# miniecu-v1_0c.net
KiCad netlist of a schematic drawn in EAGLE
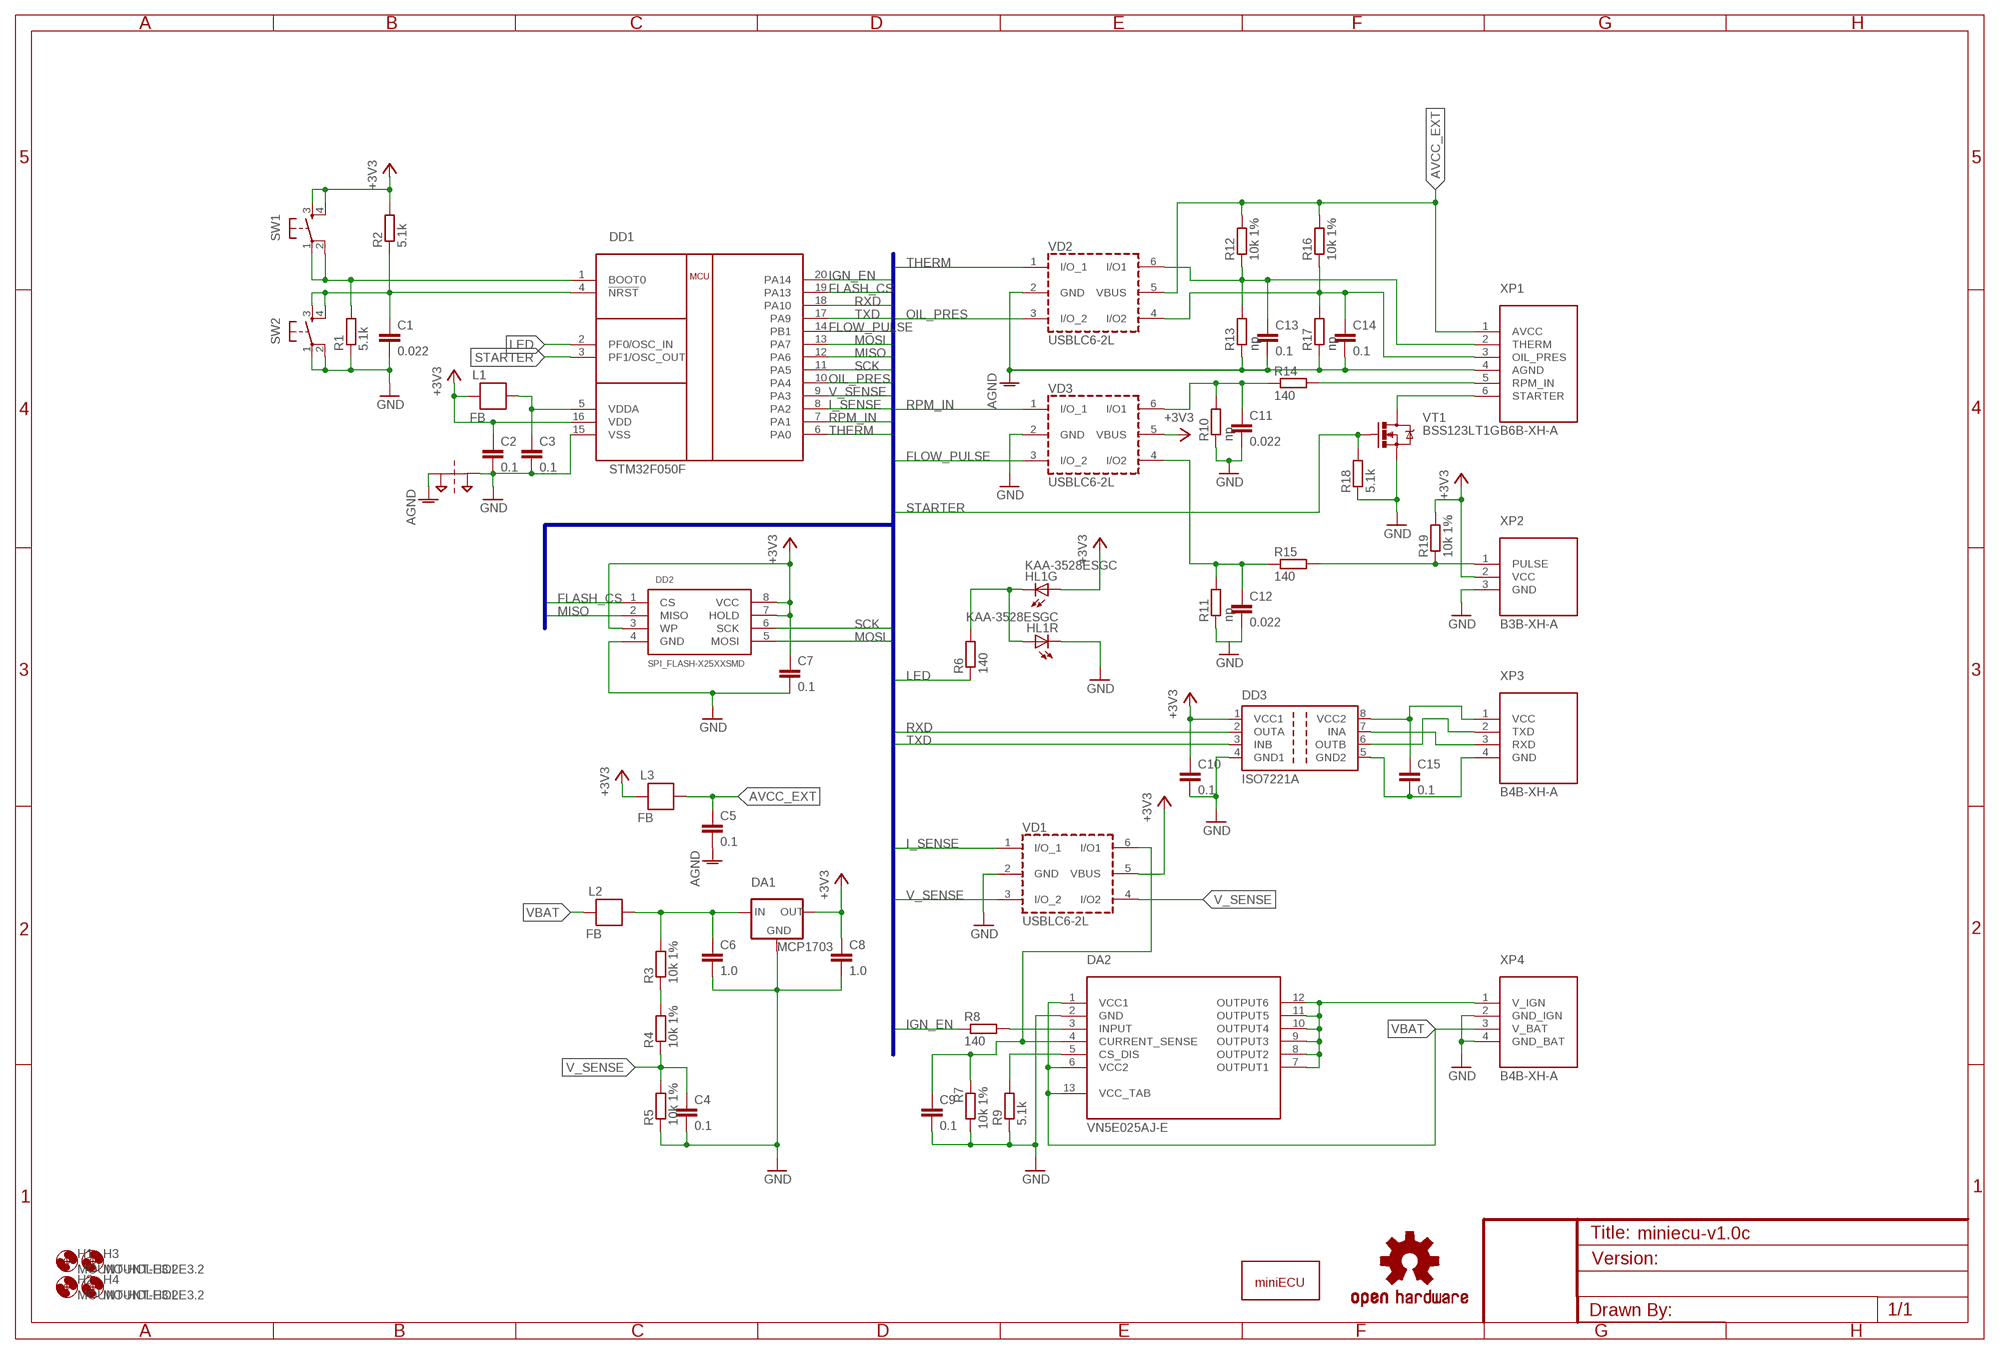
[diagram p0: schematic, sheet 1]

(export (version "E")
  (design (tool "Eeschema 10.0.6"))
  (components
    (comp (ref "C1")
      (value "0.022")
      (footprint "eagle-import:C0603")
      (libsource (lib "eagle-import") (part "C-EUC0603"))
    )
    (comp (ref "C2")
      (value "0.1")
      (footprint "eagle-import:C0603")
      (libsource (lib "eagle-import") (part "C-EUC0603"))
    )
    (comp (ref "C3")
      (value "0.1")
      (footprint "eagle-import:C0603")
      (libsource (lib "eagle-import") (part "C-EUC0603"))
    )
    (comp (ref "C4")
      (value "0.1")
      (footprint "eagle-import:C0603")
      (libsource (lib "eagle-import") (part "C-EUC0603"))
    )
    (comp (ref "C5")
      (value "0.1")
      (footprint "eagle-import:C0603")
      (libsource (lib "eagle-import") (part "C-EUC0603"))
    )
    (comp (ref "C6")
      (value "1.0")
      (footprint "eagle-import:C0805")
      (libsource (lib "eagle-import") (part "C-EUC0805"))
    )
    (comp (ref "C7")
      (value "0.1")
      (footprint "eagle-import:C0603")
      (libsource (lib "eagle-import") (part "C-EUC0603"))
    )
    (comp (ref "C8")
      (value "1.0")
      (footprint "eagle-import:C0805")
      (libsource (lib "eagle-import") (part "C-EUC0805"))
    )
    (comp (ref "C9")
      (value "0.1")
      (footprint "eagle-import:C0603")
      (libsource (lib "eagle-import") (part "C-EUC0603"))
    )
    (comp (ref "C10")
      (value "0.1")
      (footprint "eagle-import:C0603")
      (libsource (lib "eagle-import") (part "C-EUC0603"))
    )
    (comp (ref "C11")
      (value "0.022")
      (footprint "eagle-import:C0603")
      (libsource (lib "eagle-import") (part "C-EUC0603"))
    )
    (comp (ref "C12")
      (value "0.022")
      (footprint "eagle-import:C0603")
      (libsource (lib "eagle-import") (part "C-EUC0603"))
    )
    (comp (ref "C13")
      (value "0.1")
      (footprint "eagle-import:C0603")
      (libsource (lib "eagle-import") (part "C-EUC0603"))
    )
    (comp (ref "C14")
      (value "0.1")
      (footprint "eagle-import:C0603")
      (libsource (lib "eagle-import") (part "C-EUC0603"))
    )
    (comp (ref "C15")
      (value "0.1")
      (footprint "eagle-import:C0603")
      (libsource (lib "eagle-import") (part "C-EUC0603"))
    )
    (comp (ref "DA1")
      (value "MCP1703")
      (footprint "eagle-import:SOT23")
      (libsource (lib "eagle-import") (part "MCP1700SOT-23"))
    )
    (comp (ref "DA2")
      (value "VN5E025AJ-E")
      (footprint "eagle-import:POWERSSO-12")
      (libsource (lib "eagle-import") (part "VN5E025AJ-E"))
    )
    (comp (ref "DD1")
      (value "STM32F050F")
      (footprint "eagle-import:TSSOP20")
      (libsource (lib "eagle-import") (part "STM32F050F"))
    )
    (comp (ref "DD2")
      (value "SPI_FLASH-X25XXSMD")
      (footprint "eagle-import:SO08")
      (libsource (lib "eagle-import") (part "SPI_FLASH-X25XXSMD"))
    )
    (comp (ref "DD3")
      (value "ISO7221A")
      (footprint "eagle-import:SO-08")
      (fields (field (name "MPN") "ISO7221AD"))
      (libsource (lib "eagle-import") (part "ISO7221A"))
    )
    (comp (ref "H1")
      (value "MOUNT-HOLE3.2")
      (footprint "eagle-import:3,2")
      (libsource (lib "eagle-import") (part "MOUNT-HOLE3.2"))
    )
    (comp (ref "H2")
      (value "MOUNT-HOLE3.2")
      (footprint "eagle-import:3,2")
      (libsource (lib "eagle-import") (part "MOUNT-HOLE3.2"))
    )
    (comp (ref "H3")
      (value "MOUNT-HOLE3.2")
      (footprint "eagle-import:3,2")
      (libsource (lib "eagle-import") (part "MOUNT-HOLE3.2"))
    )
    (comp (ref "H4")
      (value "MOUNT-HOLE3.2")
      (footprint "eagle-import:3,2")
      (libsource (lib "eagle-import") (part "MOUNT-HOLE3.2"))
    )
    (comp (ref "HL1")
      (value "KAA-3528ESGC")
      (footprint "eagle-import:KA-3528")
      (libsource (lib "eagle-import") (part "KAA-3528ESGC"))
    )
    (comp (ref "L1")
      (value "FB")
      (footprint "eagle-import:0603")
      (libsource (lib "eagle-import") (part "FB"))
    )
    (comp (ref "L2")
      (value "FB")
      (footprint "eagle-import:0603")
      (libsource (lib "eagle-import") (part "FB"))
    )
    (comp (ref "L3")
      (value "FB")
      (footprint "eagle-import:0603")
      (libsource (lib "eagle-import") (part "FB"))
    )
    (comp (ref "LOGO1")
      (value "OSHW-LOGOL")
      (footprint "eagle-import:OSHW-LOGO-L")
      (libsource (lib "eagle-import") (part "OSHW-LOGOL"))
    )
    (comp (ref "LOGO2")
      (value "MINIECU_LOGO")
      (footprint "eagle-import:MINIECU_LOGO")
      (libsource (lib "eagle-import") (part "MINIECU_LOGO"))
    )
    (comp (ref "PT1")
      (value "2PT_GND_TIE")
      (footprint "eagle-import:2PT_GND_TIE")
      (libsource (lib "eagle-import") (part "2PT_GND_TIE"))
    )
    (comp (ref "R1")
      (value "5.1k")
      (footprint "eagle-import:R0603")
      (libsource (lib "eagle-import") (part "R-EU_R0603"))
    )
    (comp (ref "R2")
      (value "5.1k")
      (footprint "eagle-import:R0603")
      (libsource (lib "eagle-import") (part "R-EU_R0603"))
    )
    (comp (ref "R3")
      (value "10k 1%")
      (footprint "eagle-import:R0805")
      (libsource (lib "eagle-import") (part "R-EU_R0805"))
    )
    (comp (ref "R4")
      (value "10k 1%")
      (footprint "eagle-import:R0805")
      (libsource (lib "eagle-import") (part "R-EU_R0805"))
    )
    (comp (ref "R5")
      (value "10k 1%")
      (footprint "eagle-import:R0805")
      (libsource (lib "eagle-import") (part "R-EU_R0805"))
    )
    (comp (ref "R6")
      (value "140")
      (footprint "eagle-import:R0603")
      (libsource (lib "eagle-import") (part "R-EU_R0603"))
    )
    (comp (ref "R7")
      (value "10k 1%")
      (footprint "eagle-import:R0805")
      (libsource (lib "eagle-import") (part "R-EU_R0805"))
    )
    (comp (ref "R8")
      (value "140")
      (footprint "eagle-import:R0603")
      (libsource (lib "eagle-import") (part "R-EU_R0603"))
    )
    (comp (ref "R9")
      (value "5.1k")
      (footprint "eagle-import:R0603")
      (libsource (lib "eagle-import") (part "R-EU_R0603"))
    )
    (comp (ref "R10")
      (value "np")
      (footprint "eagle-import:R0603")
      (libsource (lib "eagle-import") (part "R-EU_R0603"))
    )
    (comp (ref "R11")
      (value "np")
      (footprint "eagle-import:R0603")
      (libsource (lib "eagle-import") (part "R-EU_R0603"))
    )
    (comp (ref "R12")
      (value "10k 1%")
      (footprint "eagle-import:R0805")
      (libsource (lib "eagle-import") (part "R-EU_R0805"))
    )
    (comp (ref "R13")
      (value "np")
      (footprint "eagle-import:R0805")
      (libsource (lib "eagle-import") (part "R-EU_R0805"))
    )
    (comp (ref "R14")
      (value "140")
      (footprint "eagle-import:R0603")
      (libsource (lib "eagle-import") (part "R-EU_R0603"))
    )
    (comp (ref "R15")
      (value "140")
      (footprint "eagle-import:R0603")
      (libsource (lib "eagle-import") (part "R-EU_R0603"))
    )
    (comp (ref "R16")
      (value "10k 1%")
      (footprint "eagle-import:R0805")
      (libsource (lib "eagle-import") (part "R-EU_R0805"))
    )
    (comp (ref "R17")
      (value "np")
      (footprint "eagle-import:R0805")
      (libsource (lib "eagle-import") (part "R-EU_R0805"))
    )
    (comp (ref "R18")
      (value "5.1k")
      (footprint "eagle-import:R0603")
      (libsource (lib "eagle-import") (part "R-EU_R0603"))
    )
    (comp (ref "R19")
      (value "10k 1%")
      (footprint "eagle-import:R0805")
      (libsource (lib "eagle-import") (part "R-EU_R0805"))
    )
    (comp (ref "SW1")
      (value "TAC_SWITCHSMD")
      (footprint "eagle-import:TACTILE_SWITCH_SMD")
      (libsource (lib "eagle-import") (part "TAC_SWITCHSMD"))
    )
    (comp (ref "SW2")
      (value "TAC_SWITCHSMD")
      (footprint "eagle-import:TACTILE_SWITCH_SMD")
      (libsource (lib "eagle-import") (part "TAC_SWITCHSMD"))
    )
    (comp (ref "VD1")
      (value "USBLC6-2L")
      (footprint "eagle-import:SOT-23-6L")
      (libsource (lib "eagle-import") (part "USBLC6-2SC6"))
    )
    (comp (ref "VD2")
      (value "USBLC6-2L")
      (footprint "eagle-import:SOT-23-6L")
      (libsource (lib "eagle-import") (part "USBLC6-2SC6"))
    )
    (comp (ref "VD3")
      (value "USBLC6-2L")
      (footprint "eagle-import:SOT-23-6L")
      (libsource (lib "eagle-import") (part "USBLC6-2SC6"))
    )
    (comp (ref "VT1")
      (value "BSS123LT1G")
      (footprint "eagle-import:SOT23")
      (libsource (lib "eagle-import") (part "MOSFET-NCHANNELBSS123LT1G"))
    )
    (comp (ref "XP1")
      (value "B6B-XH-A")
      (footprint "eagle-import:B6B-XH")
      (libsource (lib "eagle-import") (part "SENSORS-B6B-XH-A"))
    )
    (comp (ref "XP2")
      (value "B3B-XH-A")
      (footprint "eagle-import:B3B-XH")
      (libsource (lib "eagle-import") (part "FLOW_SENS-B3B-XH-A"))
    )
    (comp (ref "XP3")
      (value "B4B-XH-A")
      (footprint "eagle-import:B4B-XH")
      (libsource (lib "eagle-import") (part "UART-B4B-XH-A"))
    )
    (comp (ref "XP4")
      (value "B4B-XH-A")
      (footprint "eagle-import:B4B-XH")
      (libsource (lib "eagle-import") (part "IGN_POWER-B4B-XH-A"))
    )
  )
  (nets
    (net (code "1") (name "+3V3") (class "Default")
      (node (ref "C10") (pin "1") (pinfunction "1_1") (pintype "passive"))
      (node (ref "C2") (pin "1") (pinfunction "1_1") (pintype "passive"))
      (node (ref "C7") (pin "1") (pinfunction "1_1") (pintype "passive"))
      (node (ref "C8") (pin "1") (pinfunction "1_1") (pintype "passive"))
      (node (ref "DA1") (pin "2") (pinfunction "OUT_2") (pintype "passive"))
      (node (ref "DD1") (pin "16") (pinfunction "VDD_16") (pintype "power_in"))
      (node (ref "DD2") (pin "3") (pinfunction "WP_3") (pintype "bidirectional"))
      (node (ref "DD2") (pin "7") (pinfunction "HOLD_7") (pintype "bidirectional"))
      (node (ref "DD2") (pin "8") (pinfunction "VCC_8") (pintype "bidirectional"))
      (node (ref "DD3") (pin "1") (pinfunction "VCC1_1") (pintype "power_in"))
      (node (ref "HL1") (pin "4") (pinfunction "A_4") (pintype "passive"))
      (node (ref "L1") (pin "2") (pinfunction "P$2_2") (pintype "bidirectional"))
      (node (ref "L3") (pin "2") (pinfunction "P$2_2") (pintype "bidirectional"))
      (node (ref "R19") (pin "2") (pinfunction "2_2") (pintype "passive"))
      (node (ref "R2") (pin "2") (pinfunction "2_2") (pintype "passive"))
      (node (ref "SW1") (pin "3") (pinfunction "3_3") (pintype "passive"))
      (node (ref "SW1") (pin "4") (pinfunction "4_4") (pintype "passive"))
      (node (ref "VD1") (pin "5") (pinfunction "VBUS_5") (pintype "bidirectional"))
      (node (ref "VD3") (pin "5") (pinfunction "VBUS_5") (pintype "bidirectional"))
      (node (ref "XP2") (pin "2") (pinfunction "VCC_2") (pintype "passive"))
    )
    (net (code "2") (name "/FLASH_CS") (class "Default")
      (node (ref "DD1") (pin "19") (pinfunction "PA13_19") (pintype "bidirectional"))
      (node (ref "DD2") (pin "1") (pinfunction "CS_1") (pintype "bidirectional"))
    )
    (net (code "3") (name "/FLOW_PULSE") (class "Default")
      (node (ref "C12") (pin "1") (pinfunction "1_1") (pintype "passive"))
      (node (ref "DD1") (pin "14") (pinfunction "PB1_14") (pintype "bidirectional"))
      (node (ref "R11") (pin "2") (pinfunction "2_2") (pintype "passive"))
      (node (ref "R15") (pin "1") (pinfunction "1_1") (pintype "passive"))
      (node (ref "VD3") (pin "3") (pinfunction "I/O_2_3") (pintype "bidirectional"))
      (node (ref "VD3") (pin "4") (pinfunction "I/O2_4") (pintype "bidirectional"))
    )
    (net (code "4") (name "/IGN_EN") (class "Default")
      (node (ref "DD1") (pin "20") (pinfunction "PA14_20") (pintype "bidirectional"))
      (node (ref "R8") (pin "1") (pinfunction "1_1") (pintype "passive"))
    )
    (net (code "5") (name "/I_SENSE") (class "Default")
      (node (ref "C9") (pin "1") (pinfunction "1_1") (pintype "passive"))
      (node (ref "DA2") (pin "4") (pinfunction "CURRENT_SENSE_4") (pintype "bidirectional"))
      (node (ref "DD1") (pin "8") (pinfunction "PA2_8") (pintype "bidirectional"))
      (node (ref "R7") (pin "1") (pinfunction "1_1") (pintype "passive"))
      (node (ref "VD1") (pin "1") (pinfunction "I/O_1_1") (pintype "bidirectional"))
      (node (ref "VD1") (pin "6") (pinfunction "I/O1_6") (pintype "bidirectional"))
    )
    (net (code "6") (name "/MISO") (class "Default")
      (node (ref "DD1") (pin "12") (pinfunction "PA6_12") (pintype "bidirectional"))
      (node (ref "DD2") (pin "2") (pinfunction "MISO_2") (pintype "bidirectional"))
    )
    (net (code "7") (name "/MOSI") (class "Default")
      (node (ref "DD1") (pin "13") (pinfunction "PA7_13") (pintype "bidirectional"))
      (node (ref "DD2") (pin "5") (pinfunction "MOSI_5") (pintype "bidirectional"))
    )
    (net (code "8") (name "/OIL_PRES") (class "Default")
      (node (ref "C14") (pin "1") (pinfunction "1_1") (pintype "passive"))
      (node (ref "DD1") (pin "10") (pinfunction "PA4_10") (pintype "bidirectional"))
      (node (ref "R16") (pin "1") (pinfunction "1_1") (pintype "passive"))
      (node (ref "R17") (pin "2") (pinfunction "2_2") (pintype "passive"))
      (node (ref "VD2") (pin "3") (pinfunction "I/O_2_3") (pintype "bidirectional"))
      (node (ref "VD2") (pin "4") (pinfunction "I/O2_4") (pintype "bidirectional"))
      (node (ref "XP1") (pin "3") (pinfunction "OIL_PRES_3") (pintype "passive"))
    )
    (net (code "9") (name "/RPM_IN") (class "Default")
      (node (ref "C11") (pin "1") (pinfunction "1_1") (pintype "passive"))
      (node (ref "DD1") (pin "7") (pinfunction "PA1_7") (pintype "bidirectional"))
      (node (ref "R10") (pin "2") (pinfunction "2_2") (pintype "passive"))
      (node (ref "R14") (pin "1") (pinfunction "1_1") (pintype "passive"))
      (node (ref "VD3") (pin "1") (pinfunction "I/O_1_1") (pintype "bidirectional"))
      (node (ref "VD3") (pin "6") (pinfunction "I/O1_6") (pintype "bidirectional"))
    )
    (net (code "10") (name "/RXD") (class "Default")
      (node (ref "DD1") (pin "18") (pinfunction "PA10_18") (pintype "bidirectional"))
      (node (ref "DD3") (pin "2") (pinfunction "OUTA_2") (pintype "output"))
    )
    (net (code "11") (name "/SCK") (class "Default")
      (node (ref "DD1") (pin "11") (pinfunction "PA5_11") (pintype "bidirectional"))
      (node (ref "DD2") (pin "6") (pinfunction "SCK_6") (pintype "bidirectional"))
    )
    (net (code "12") (name "/THERM") (class "Default")
      (node (ref "C13") (pin "1") (pinfunction "1_1") (pintype "passive"))
      (node (ref "DD1") (pin "6") (pinfunction "PA0_6") (pintype "bidirectional"))
      (node (ref "R12") (pin "1") (pinfunction "1_1") (pintype "passive"))
      (node (ref "R13") (pin "2") (pinfunction "2_2") (pintype "passive"))
      (node (ref "VD2") (pin "1") (pinfunction "I/O_1_1") (pintype "bidirectional"))
      (node (ref "VD2") (pin "6") (pinfunction "I/O1_6") (pintype "bidirectional"))
      (node (ref "XP1") (pin "2") (pinfunction "THERM_2") (pintype "passive"))
    )
    (net (code "13") (name "/TXD") (class "Default")
      (node (ref "DD1") (pin "17") (pinfunction "PA9_17") (pintype "bidirectional"))
      (node (ref "DD3") (pin "3") (pinfunction "INB_3") (pintype "input"))
    )
    (net (code "14") (name "AGND") (class "Default")
      (node (ref "C13") (pin "2") (pinfunction "2_2") (pintype "passive"))
      (node (ref "C14") (pin "2") (pinfunction "2_2") (pintype "passive"))
      (node (ref "C5") (pin "2") (pinfunction "2_2") (pintype "passive"))
      (node (ref "PT1") (pin "P$1") (pinfunction "P$1_P$1") (pintype "bidirectional"))
      (node (ref "R13") (pin "1") (pinfunction "1_1") (pintype "passive"))
      (node (ref "R17") (pin "1") (pinfunction "1_1") (pintype "passive"))
      (node (ref "VD2") (pin "2") (pinfunction "GND_2") (pintype "bidirectional"))
      (node (ref "XP1") (pin "4") (pinfunction "AGND_4") (pintype "passive"))
    )
    (net (code "15") (name "AVCC_EXT") (class "Default")
      (node (ref "C5") (pin "1") (pinfunction "1_1") (pintype "passive"))
      (node (ref "L3") (pin "1") (pinfunction "P$1_1") (pintype "bidirectional"))
      (node (ref "R12") (pin "2") (pinfunction "2_2") (pintype "passive"))
      (node (ref "R16") (pin "2") (pinfunction "2_2") (pintype "passive"))
      (node (ref "VD2") (pin "5") (pinfunction "VBUS_5") (pintype "bidirectional"))
      (node (ref "XP1") (pin "1") (pinfunction "AVCC_1") (pintype "passive"))
    )
    (net (code "16") (name "GND") (class "Default")
      (node (ref "C1") (pin "2") (pinfunction "2_2") (pintype "passive"))
      (node (ref "C10") (pin "2") (pinfunction "2_2") (pintype "passive"))
      (node (ref "C11") (pin "2") (pinfunction "2_2") (pintype "passive"))
      (node (ref "C12") (pin "2") (pinfunction "2_2") (pintype "passive"))
      (node (ref "C2") (pin "2") (pinfunction "2_2") (pintype "passive"))
      (node (ref "C3") (pin "2") (pinfunction "2_2") (pintype "passive"))
      (node (ref "C4") (pin "2") (pinfunction "2_2") (pintype "passive"))
      (node (ref "C6") (pin "2") (pinfunction "2_2") (pintype "passive"))
      (node (ref "C7") (pin "2") (pinfunction "2_2") (pintype "passive"))
      (node (ref "C8") (pin "2") (pinfunction "2_2") (pintype "passive"))
      (node (ref "C9") (pin "2") (pinfunction "2_2") (pintype "passive"))
      (node (ref "DA1") (pin "1") (pinfunction "GND_1") (pintype "input"))
      (node (ref "DA2") (pin "2") (pinfunction "GND_2") (pintype "power_in"))
      (node (ref "DD1") (pin "15") (pinfunction "VSS_15") (pintype "power_in"))
      (node (ref "DD2") (pin "4") (pinfunction "GND_4") (pintype "bidirectional"))
      (node (ref "DD3") (pin "4") (pinfunction "GND1_4") (pintype "power_in"))
      (node (ref "HL1") (pin "1") (pinfunction "C_1") (pintype "passive"))
      (node (ref "PT1") (pin "P$2") (pinfunction "P$2_P$2") (pintype "bidirectional"))
      (node (ref "R1") (pin "1") (pinfunction "1_1") (pintype "passive"))
      (node (ref "R10") (pin "1") (pinfunction "1_1") (pintype "passive"))
      (node (ref "R11") (pin "1") (pinfunction "1_1") (pintype "passive"))
      (node (ref "R18") (pin "1") (pinfunction "1_1") (pintype "passive"))
      (node (ref "R5") (pin "1") (pinfunction "1_1") (pintype "passive"))
      (node (ref "R7") (pin "2") (pinfunction "2_2") (pintype "passive"))
      (node (ref "R9") (pin "1") (pinfunction "1_1") (pintype "passive"))
      (node (ref "SW2") (pin "1") (pinfunction "1_1") (pintype "passive"))
      (node (ref "SW2") (pin "2") (pinfunction "2_2") (pintype "passive"))
      (node (ref "VD1") (pin "2") (pinfunction "GND_2") (pintype "bidirectional"))
      (node (ref "VD3") (pin "2") (pinfunction "GND_2") (pintype "bidirectional"))
      (node (ref "VT1") (pin "2") (pinfunction "S_2") (pintype "passive"))
      (node (ref "XP2") (pin "3") (pinfunction "GND_3") (pintype "passive"))
      (node (ref "XP4") (pin "2") (pinfunction "GND_IGN_2") (pintype "passive"))
      (node (ref "XP4") (pin "4") (pinfunction "GND_BAT_4") (pintype "passive"))
    )
    (net (code "17") (name "LED") (class "Default")
      (node (ref "DD1") (pin "2") (pinfunction "PF0/OSC_IN_2") (pintype "bidirectional"))
      (node (ref "R6") (pin "1") (pinfunction "1_1") (pintype "passive"))
    )
    (net (code "18") (name "Net-(DA1-IN)") (class "Default")
      (node (ref "C6") (pin "1") (pinfunction "1_1") (pintype "passive"))
      (node (ref "DA1") (pin "3") (pinfunction "IN_3") (pintype "input"))
      (node (ref "L2") (pin "1") (pinfunction "P$1_1") (pintype "bidirectional"))
      (node (ref "R3") (pin "2") (pinfunction "2_2") (pintype "passive"))
    )
    (net (code "19") (name "Net-(DA2-CS_DIS)") (class "Default")
      (node (ref "DA2") (pin "5") (pinfunction "CS_DIS_5") (pintype "input"))
      (node (ref "R9") (pin "2") (pinfunction "2_2") (pintype "passive"))
    )
    (net (code "20") (name "Net-(DA2-INPUT)") (class "Default")
      (node (ref "DA2") (pin "3") (pinfunction "INPUT_3") (pintype "input"))
      (node (ref "R8") (pin "2") (pinfunction "2_2") (pintype "passive"))
    )
    (net (code "21") (name "Net-(DA2-OUTPUT1)") (class "Default")
      (node (ref "DA2") (pin "10") (pinfunction "OUTPUT4_10") (pintype "power_in"))
      (node (ref "DA2") (pin "11") (pinfunction "OUTPUT5_11") (pintype "power_in"))
      (node (ref "DA2") (pin "12") (pinfunction "OUTPUT6_12") (pintype "power_in"))
      (node (ref "DA2") (pin "7") (pinfunction "OUTPUT1_7") (pintype "power_in"))
      (node (ref "DA2") (pin "8") (pinfunction "OUTPUT2_8") (pintype "power_in"))
      (node (ref "DA2") (pin "9") (pinfunction "OUTPUT3_9") (pintype "power_in"))
      (node (ref "XP4") (pin "1") (pinfunction "V_IGN_1") (pintype "passive"))
    )
    (net (code "22") (name "Net-(DD1-BOOT0)") (class "Default")
      (node (ref "DD1") (pin "1") (pinfunction "BOOT0_1") (pintype "input"))
      (node (ref "R1") (pin "2") (pinfunction "2_2") (pintype "passive"))
      (node (ref "SW1") (pin "1") (pinfunction "1_1") (pintype "passive"))
      (node (ref "SW1") (pin "2") (pinfunction "2_2") (pintype "passive"))
    )
    (net (code "23") (name "Net-(DD1-VDDA)") (class "Default")
      (node (ref "C3") (pin "1") (pinfunction "1_1") (pintype "passive"))
      (node (ref "DD1") (pin "5") (pinfunction "VDDA_5") (pintype "power_in"))
      (node (ref "L1") (pin "1") (pinfunction "P$1_1") (pintype "bidirectional"))
    )
    (net (code "24") (name "Net-(DD1-~{NRST})") (class "Default")
      (node (ref "C1") (pin "1") (pinfunction "1_1") (pintype "passive"))
      (node (ref "DD1") (pin "4") (pinfunction "~{NRST}_4") (pintype "input"))
      (node (ref "R2") (pin "1") (pinfunction "1_1") (pintype "passive"))
      (node (ref "SW2") (pin "3") (pinfunction "3_3") (pintype "passive"))
      (node (ref "SW2") (pin "4") (pinfunction "4_4") (pintype "passive"))
    )
    (net (code "25") (name "Net-(DD3-GND2)") (class "Default")
      (node (ref "C15") (pin "2") (pinfunction "2_2") (pintype "passive"))
      (node (ref "DD3") (pin "5") (pinfunction "GND2_5") (pintype "power_in"))
      (node (ref "XP3") (pin "4") (pinfunction "GND_4") (pintype "passive"))
    )
    (net (code "26") (name "Net-(DD3-INA)") (class "Default")
      (node (ref "DD3") (pin "7") (pinfunction "INA_7") (pintype "input"))
      (node (ref "XP3") (pin "3") (pinfunction "RXD_3") (pintype "passive"))
    )
    (net (code "27") (name "Net-(DD3-OUTB)") (class "Default")
      (node (ref "DD3") (pin "6") (pinfunction "OUTB_6") (pintype "output"))
      (node (ref "XP3") (pin "2") (pinfunction "TXD_2") (pintype "passive"))
    )
    (net (code "28") (name "Net-(DD3-VCC2)") (class "Default")
      (node (ref "C15") (pin "1") (pinfunction "1_1") (pintype "passive"))
      (node (ref "DD3") (pin "8") (pinfunction "VCC2_8") (pintype "power_in"))
      (node (ref "XP3") (pin "1") (pinfunction "VCC_1") (pintype "passive"))
    )
    (net (code "29") (name "Net-(HL1A-C)") (class "Default")
      (node (ref "HL1") (pin "2") (pinfunction "A_2") (pintype "passive"))
      (node (ref "HL1") (pin "3") (pinfunction "C_3") (pintype "passive"))
      (node (ref "R6") (pin "2") (pinfunction "2_2") (pintype "passive"))
    )
    (net (code "30") (name "Net-(R3-Pad1)") (class "Default")
      (node (ref "R3") (pin "1") (pinfunction "1_1") (pintype "passive"))
      (node (ref "R4") (pin "2") (pinfunction "2_2") (pintype "passive"))
    )
    (net (code "31") (name "Net-(VT1-D)") (class "Default")
      (node (ref "VT1") (pin "3") (pinfunction "D_3") (pintype "passive"))
      (node (ref "XP1") (pin "6") (pinfunction "STARTER_6") (pintype "passive"))
    )
    (net (code "32") (name "Net-(XP1-RPM_IN)") (class "Default")
      (node (ref "R14") (pin "2") (pinfunction "2_2") (pintype "passive"))
      (node (ref "XP1") (pin "5") (pinfunction "RPM_IN_5") (pintype "passive"))
    )
    (net (code "33") (name "Net-(XP2-PULSE)") (class "Default")
      (node (ref "R15") (pin "2") (pinfunction "2_2") (pintype "passive"))
      (node (ref "R19") (pin "1") (pinfunction "1_1") (pintype "passive"))
      (node (ref "XP2") (pin "1") (pinfunction "PULSE_1") (pintype "passive"))
    )
    (net (code "34") (name "STARTER") (class "Default")
      (node (ref "DD1") (pin "3") (pinfunction "PF1/OSC_OUT_3") (pintype "bidirectional"))
      (node (ref "R18") (pin "2") (pinfunction "2_2") (pintype "passive"))
      (node (ref "VT1") (pin "1") (pinfunction "G_1") (pintype "passive"))
    )
    (net (code "35") (name "VBAT") (class "Default")
      (node (ref "DA2") (pin "1") (pinfunction "VCC1_1") (pintype "power_in"))
      (node (ref "DA2") (pin "13") (pinfunction "VCC_TAB_13") (pintype "power_in"))
      (node (ref "DA2") (pin "6") (pinfunction "VCC2_6") (pintype "power_in"))
      (node (ref "L2") (pin "2") (pinfunction "P$2_2") (pintype "bidirectional"))
      (node (ref "XP4") (pin "3") (pinfunction "V_BAT_3") (pintype "passive"))
    )
    (net (code "36") (name "V_SENSE") (class "Default")
      (node (ref "C4") (pin "1") (pinfunction "1_1") (pintype "passive"))
      (node (ref "DD1") (pin "9") (pinfunction "PA3_9") (pintype "bidirectional"))
      (node (ref "R4") (pin "1") (pinfunction "1_1") (pintype "passive"))
      (node (ref "R5") (pin "2") (pinfunction "2_2") (pintype "passive"))
      (node (ref "VD1") (pin "3") (pinfunction "I/O_2_3") (pintype "bidirectional"))
      (node (ref "VD1") (pin "4") (pinfunction "I/O2_4") (pintype "bidirectional"))
    )
  )
)
